# Qwiic_Lidar_Lite.net
KiCad netlist of a schematic drawn in EAGLE
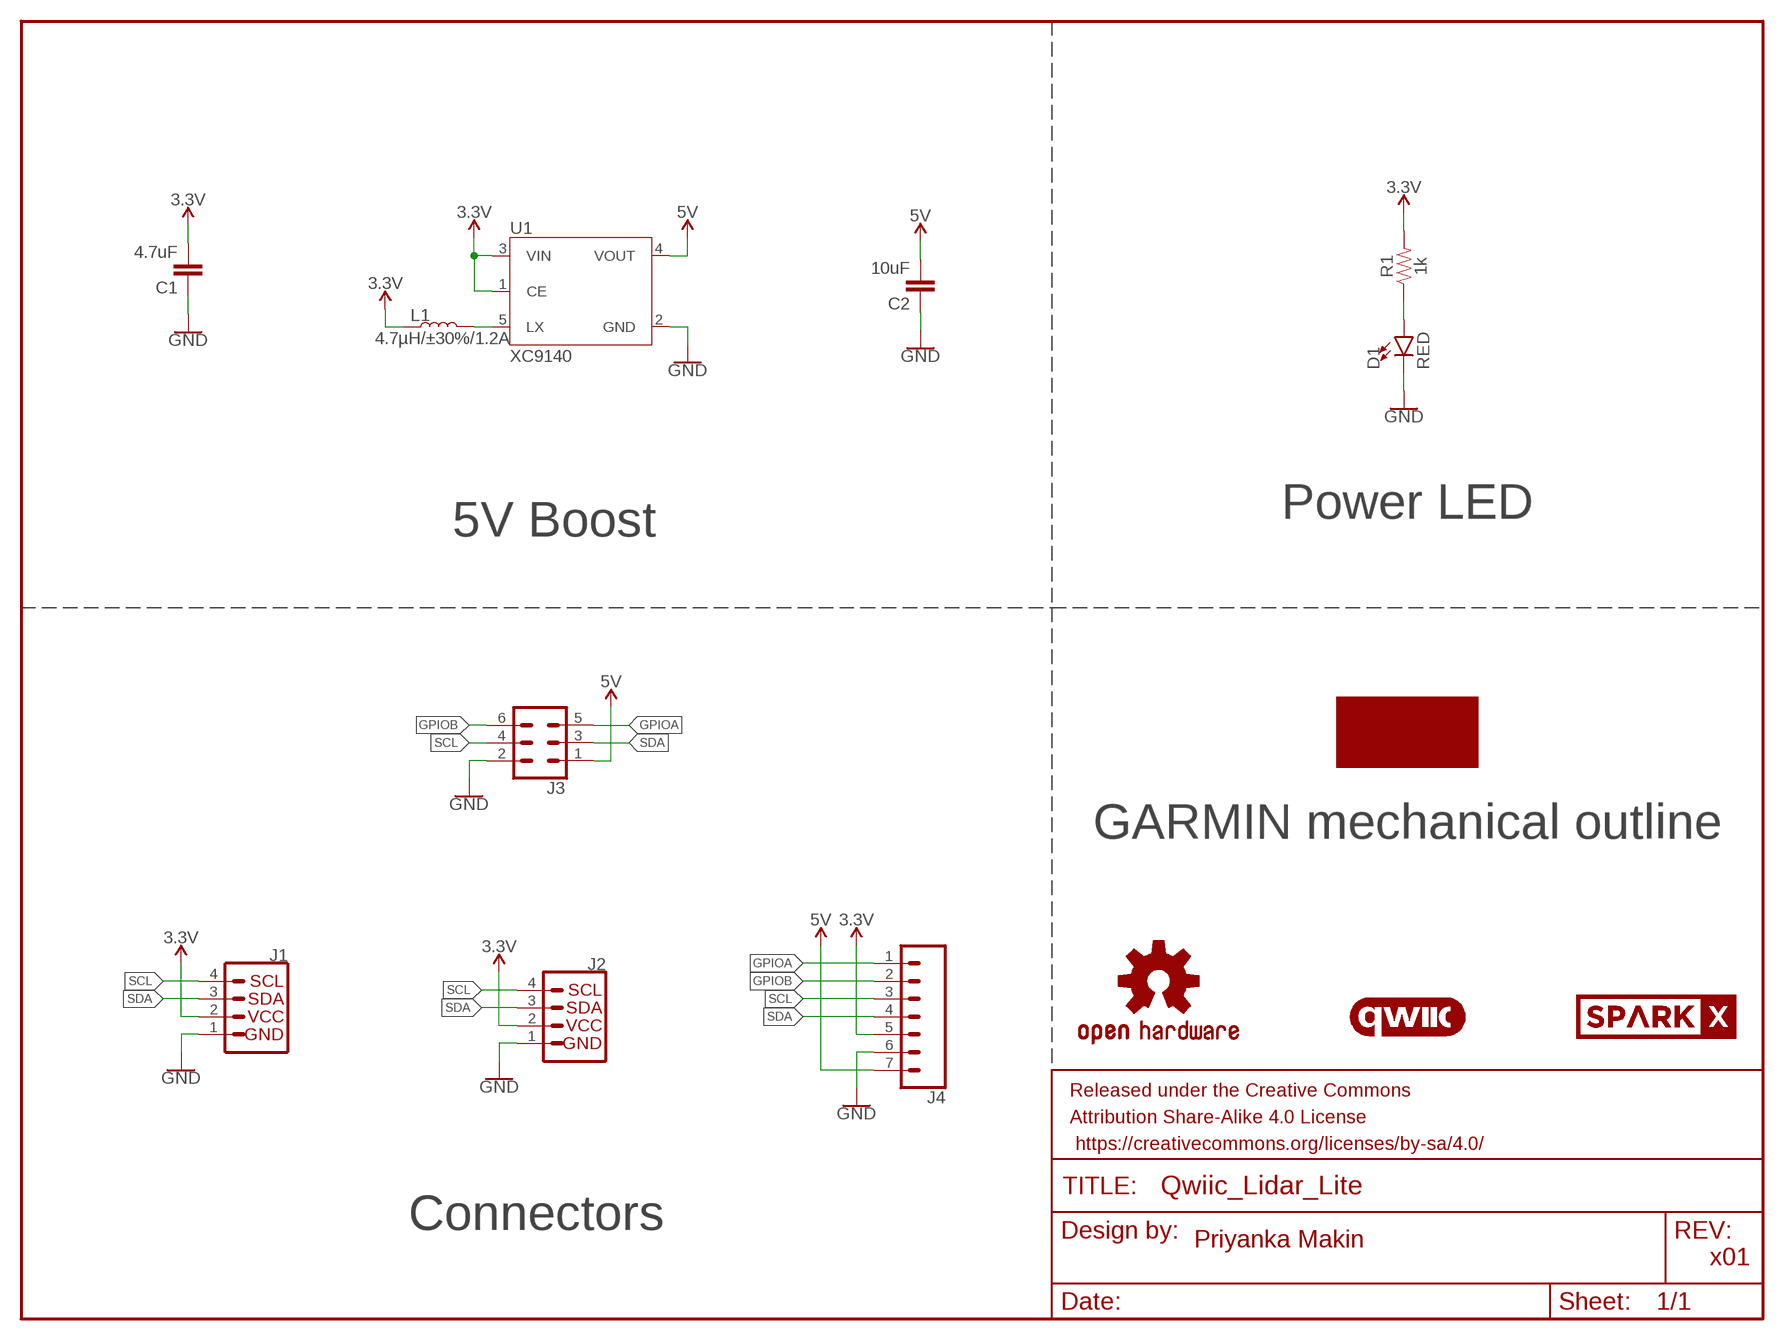
[diagram p0: schematic, sheet 1]

(export (version "E")
  (design (tool "Eeschema 10.0.6"))
  (components
    (comp (ref "C1")
      (value "4.7uF")
      (footprint "eagle-import:0603")
      (libsource (lib "eagle-import") (part "4.7UF-0603-6.3V-(10%)"))
    )
    (comp (ref "C2")
      (value "10uF")
      (footprint "eagle-import:0603")
      (libsource (lib "eagle-import") (part "10UF-0603-6.3V-20%"))
    )
    (comp (ref "D1")
      (value "RED")
      (footprint "eagle-import:LED-0603")
      (libsource (lib "eagle-import") (part "LED-RED0603"))
    )
    (comp (ref "FRAME1")
      (value "FRAME-LETTER")
      (footprint "eagle-import:CREATIVE_COMMONS")
      (libsource (lib "eagle-import") (part "FRAME-LETTER"))
    )
    (comp (ref "J1")
      (value "QWIIC_CONNECTORJS-1MM")
      (footprint "eagle-import:JST04_1MM_RA")
      (libsource (lib "eagle-import") (part "QWIIC_CONNECTORJS-1MM"))
    )
    (comp (ref "J2")
      (value "QWIIC_CONNECTORJS-1MM")
      (footprint "eagle-import:JST04_1MM_RA")
      (libsource (lib "eagle-import") (part "QWIIC_CONNECTORJS-1MM"))
    )
    (comp (ref "J3")
      (value "CONN_03X22MM")
      (footprint "eagle-import:CONN_3X2_2MM")
      (libsource (lib "eagle-import") (part "CONN_03X22MM"))
    )
    (comp (ref "J4")
      (value "CONN_07NO_SILK")
      (footprint "eagle-import:1X07_NO_SILK")
      (libsource (lib "eagle-import") (part "CONN_07NO_SILK"))
    )
    (comp (ref "L1")
      (value "4.7µH/±30%/1.2A")
      (footprint "eagle-import:INDUCTOR_4.7UH")
      (libsource (lib "eagle-import") (part "INDUCTOR-CDRH-4.7UH"))
    )
    (comp (ref "LOGO1")
      (value "QWIIC_LOGO_CONNECTOR")
      (footprint "eagle-import:QWIIC_5.5MM")
      (libsource (lib "eagle-import") (part "QWIIC_LOGO_CONNECTOR"))
    )
    (comp (ref "LOGO2")
      (value "OSHW-LOGOMINI")
      (footprint "eagle-import:OSHW-LOGO-MINI")
      (libsource (lib "eagle-import") (part "OSHW-LOGOMINI"))
    )
    (comp (ref "R1")
      (value "1k")
      (footprint "eagle-import:0603")
      (libsource (lib "eagle-import") (part "1KOHM-0603-1/10W-1%"))
    )
    (comp (ref "U$7")
      (value "LIDAR_LITE")
      (footprint "eagle-import:LIDAR_LITE")
      (libsource (lib "eagle-import") (part "LIDAR_LITE"))
    )
    (comp (ref "U$8")
      (value "SPARKX-LOGO4")
      (footprint "eagle-import:SPARKX-MEDIUM")
      (libsource (lib "eagle-import") (part "SPARKX-LOGO4"))
    )
    (comp (ref "U1")
      (value "XC9140")
      (footprint "eagle-import:SOT23-5")
      (libsource (lib "eagle-import") (part "XC9140"))
    )
  )
  (nets
    (net (code "1") (name "3.3V") (class "Default")
      (node (ref "C1") (pin "2") (pinfunction "2_2") (pintype "passive"))
      (node (ref "J1") (pin "2") (pinfunction "2_2") (pintype "power_in"))
      (node (ref "J2") (pin "2") (pinfunction "2_2") (pintype "power_in"))
      (node (ref "J4") (pin "5") (pinfunction "5_5") (pintype "passive"))
      (node (ref "L1") (pin "P$1") (pinfunction "1_P$1") (pintype "passive"))
      (node (ref "R1") (pin "2") (pinfunction "2_2") (pintype "passive"))
      (node (ref "U1") (pin "1") (pinfunction "CE_1") (pintype "input"))
      (node (ref "U1") (pin "3") (pinfunction "VIN_3") (pintype "power_in"))
    )
    (net (code "2") (name "5V") (class "Default")
      (node (ref "C2") (pin "2") (pinfunction "2_2") (pintype "passive"))
      (node (ref "J3") (pin "1") (pinfunction "1_1") (pintype "bidirectional"))
      (node (ref "J4") (pin "7") (pinfunction "7_7") (pintype "passive"))
      (node (ref "U1") (pin "4") (pinfunction "VOUT_4") (pintype "output"))
    )
    (net (code "3") (name "GND") (class "Default")
      (node (ref "C1") (pin "1") (pinfunction "1_1") (pintype "passive"))
      (node (ref "C2") (pin "1") (pinfunction "1_1") (pintype "passive"))
      (node (ref "D1") (pin "C") (pinfunction "C_C") (pintype "passive"))
      (node (ref "J1") (pin "1") (pinfunction "1_1") (pintype "power_in"))
      (node (ref "J2") (pin "1") (pinfunction "1_1") (pintype "power_in"))
      (node (ref "J3") (pin "2") (pinfunction "2_2") (pintype "bidirectional"))
      (node (ref "J4") (pin "6") (pinfunction "6_6") (pintype "passive"))
      (node (ref "U1") (pin "2") (pinfunction "GND_2") (pintype "power_in"))
    )
    (net (code "4") (name "GPIOA") (class "Default")
      (node (ref "J3") (pin "5") (pinfunction "5_5") (pintype "bidirectional"))
      (node (ref "J4") (pin "1") (pinfunction "1_1") (pintype "passive"))
    )
    (net (code "5") (name "GPIOB") (class "Default")
      (node (ref "J3") (pin "6") (pinfunction "6_6") (pintype "bidirectional"))
      (node (ref "J4") (pin "2") (pinfunction "2_2") (pintype "passive"))
    )
    (net (code "6") (name "Net-(D1-PadA)") (class "Default")
      (node (ref "D1") (pin "A") (pinfunction "A_A") (pintype "passive"))
      (node (ref "R1") (pin "1") (pinfunction "1_1") (pintype "passive"))
    )
    (net (code "7") (name "Net-(L1-2)") (class "Default")
      (node (ref "L1") (pin "P$2") (pinfunction "2_P$2") (pintype "passive"))
      (node (ref "U1") (pin "5") (pinfunction "LX_5") (pintype "input"))
    )
    (net (code "8") (name "SCL") (class "Default")
      (node (ref "J1") (pin "4") (pinfunction "4_4") (pintype "passive"))
      (node (ref "J2") (pin "4") (pinfunction "4_4") (pintype "passive"))
      (node (ref "J3") (pin "4") (pinfunction "4_4") (pintype "bidirectional"))
      (node (ref "J4") (pin "3") (pinfunction "3_3") (pintype "passive"))
    )
    (net (code "9") (name "SDA") (class "Default")
      (node (ref "J1") (pin "3") (pinfunction "3_3") (pintype "passive"))
      (node (ref "J2") (pin "3") (pinfunction "3_3") (pintype "passive"))
      (node (ref "J3") (pin "3") (pinfunction "3_3") (pintype "bidirectional"))
      (node (ref "J4") (pin "4") (pinfunction "4_4") (pintype "passive"))
    )
  )
)
